# untitled.net
KiCad netlist of a schematic drawn in EAGLE
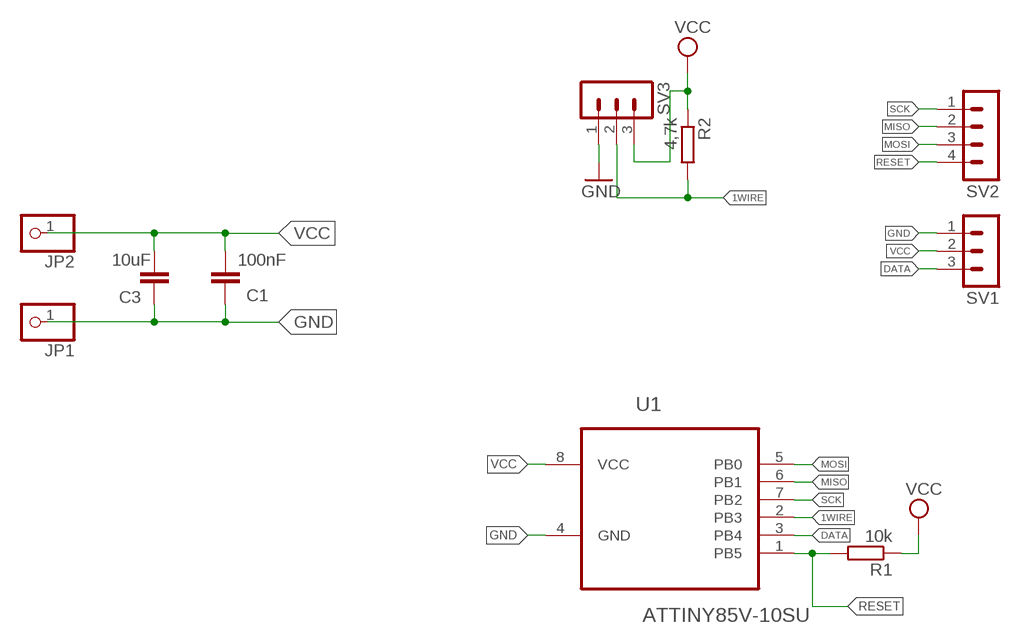
[diagram p0: schematic, sheet 1]

(export (version "E")
  (design (tool "Eeschema 10.0.6"))
  (components
    (comp (ref "C1")
      (value "100nF")
      (footprint "eagle-import:C0805")
      (libsource (lib "eagle-import") (part "C-EUC0805"))
    )
    (comp (ref "C3")
      (value "10uF")
      (footprint "eagle-import:C1206")
      (libsource (lib "eagle-import") (part "C-EUC1206"))
    )
    (comp (ref "JP1")
      (value "PINHD-1X1")
      (footprint "eagle-import:1X01")
      (libsource (lib "eagle-import") (part "PINHD-1X1"))
    )
    (comp (ref "JP2")
      (value "PINHD-1X1")
      (footprint "eagle-import:1X01")
      (libsource (lib "eagle-import") (part "PINHD-1X1"))
    )
    (comp (ref "R1")
      (value "10k")
      (footprint "eagle-import:R0805")
      (libsource (lib "eagle-import") (part "R-EU_R0805"))
    )
    (comp (ref "R2")
      (value "4,7k")
      (footprint "eagle-import:R0805")
      (libsource (lib "eagle-import") (part "R-EU_R0805"))
    )
    (comp (ref "SV1")
      (value "MA03-1")
      (footprint "eagle-import:MA03-1")
      (libsource (lib "eagle-import") (part "MA03-1"))
    )
    (comp (ref "SV2")
      (value "MA04-1")
      (footprint "eagle-import:MA04-1")
      (libsource (lib "eagle-import") (part "MA04-1"))
    )
    (comp (ref "SV3")
      (value "MA03-1")
      (footprint "eagle-import:MA03-1")
      (libsource (lib "eagle-import") (part "MA03-1"))
    )
    (comp (ref "U1")
      (value "ATTINY85V-10SU")
      (footprint "eagle-import:SOIC127P798X216-8N")
      (libsource (lib "eagle-import") (part "ATTINY85V-10SU"))
    )
  )
  (nets
    (net (code "1") (name "1WIRE") (class "Default")
      (node (ref "R2") (pin "2") (pinfunction "2_2") (pintype "passive"))
      (node (ref "SV3") (pin "2") (pinfunction "2_2") (pintype "passive"))
      (node (ref "U1") (pin "2") (pinfunction "PB3_2") (pintype "bidirectional"))
    )
    (net (code "2") (name "DATA") (class "Default")
      (node (ref "SV1") (pin "3") (pinfunction "3_3") (pintype "passive"))
      (node (ref "U1") (pin "3") (pinfunction "PB4_3") (pintype "bidirectional"))
    )
    (net (code "3") (name "GND") (class "Default")
      (node (ref "C1") (pin "1") (pinfunction "1_1") (pintype "passive"))
      (node (ref "C3") (pin "2") (pinfunction "2_2") (pintype "passive"))
      (node (ref "JP1") (pin "1") (pinfunction "1_1") (pintype "passive"))
      (node (ref "SV1") (pin "1") (pinfunction "1_1") (pintype "passive"))
      (node (ref "SV3") (pin "1") (pinfunction "1_1") (pintype "passive"))
      (node (ref "U1") (pin "4") (pinfunction "GND_4") (pintype "passive"))
    )
    (net (code "4") (name "MISO") (class "Default")
      (node (ref "SV2") (pin "2") (pinfunction "2_2") (pintype "passive"))
      (node (ref "U1") (pin "6") (pinfunction "PB1_6") (pintype "bidirectional"))
    )
    (net (code "5") (name "MOSI") (class "Default")
      (node (ref "SV2") (pin "3") (pinfunction "3_3") (pintype "passive"))
      (node (ref "U1") (pin "5") (pinfunction "PB0_5") (pintype "bidirectional"))
    )
    (net (code "6") (name "RESET") (class "Default")
      (node (ref "R1") (pin "2") (pinfunction "2_2") (pintype "passive"))
      (node (ref "SV2") (pin "4") (pinfunction "4_4") (pintype "passive"))
      (node (ref "U1") (pin "1") (pinfunction "PB5_1") (pintype "bidirectional"))
    )
    (net (code "7") (name "SCK") (class "Default")
      (node (ref "SV2") (pin "1") (pinfunction "1_1") (pintype "passive"))
      (node (ref "U1") (pin "7") (pinfunction "PB2_7") (pintype "bidirectional"))
    )
    (net (code "8") (name "VCC") (class "Default")
      (node (ref "C1") (pin "2") (pinfunction "2_2") (pintype "passive"))
      (node (ref "C3") (pin "1") (pinfunction "1_1") (pintype "passive"))
      (node (ref "JP2") (pin "1") (pinfunction "1_1") (pintype "passive"))
      (node (ref "R1") (pin "1") (pinfunction "1_1") (pintype "passive"))
      (node (ref "R2") (pin "1") (pinfunction "1_1") (pintype "passive"))
      (node (ref "SV1") (pin "2") (pinfunction "2_2") (pintype "passive"))
      (node (ref "SV3") (pin "3") (pinfunction "3_3") (pintype "passive"))
      (node (ref "U1") (pin "8") (pinfunction "VCC_8") (pintype "power_in"))
    )
  )
)
